# led_boost.net
KiCad netlist of a schematic drawn in Altium Designer
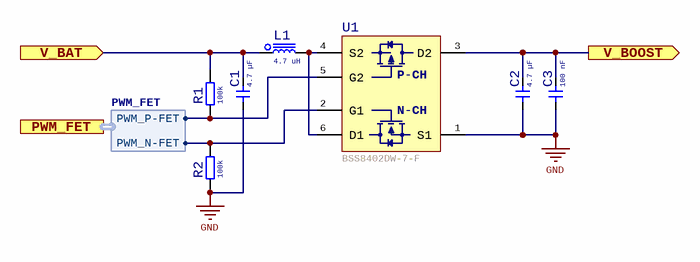
[diagram p0: led_boost.SchDoc]

(export (version "E")
  (design (tool "Eeschema 10.0.6"))
  (components
    (comp (ref "C1")
      (value "4.7 µF")
      (footprint "1608C")
      (description "SMD ceramic capacitor, X5R")
      (fields (field (name "MANUFACTURER") "Kemet") (field (name "VOLTAGE") "6,3"))
      (libsource (lib "Contronix") (part "CAP-NP"))
    )
    (comp (ref "C2")
      (value "4.7 µF")
      (footprint "1608C")
      (description "SMD ceramic capacitor, X5R")
      (fields (field (name "MANUFACTURER") "Kemet") (field (name "VOLTAGE") "6,3"))
      (libsource (lib "Contronix") (part "CAP-NP"))
    )
    (comp (ref "C3")
      (value "100 nF")
      (footprint "1005C")
      (description "SMD ceramic capacitor, X7R")
      (fields
        (field (name "MANUFACTURER") "Samsung Electro-Mechanics America, Inc.")
        (field (name "VOLTAGE") "6,3")
      )
      (libsource (lib "Contronix") (part "CAP-NP"))
    )
    (comp (ref "L1")
      (value "4.7 uH")
      (footprint "2012L")
      (description "Chip Inductor")
      (fields (field (name "MANUFACTURER") "Murata Electronics") (field (name "TOLERANCE") "30%"))
      (libsource (lib "Contronix") (part "INDUCTOR"))
    )
    (comp (ref "R1")
      (value "100k")
      (footprint "1005R")
      (description "SMD resistor")
      (fields (field (name "MANUFACTURER") "Yageo") (field (name "TOLERANCE") "1%"))
      (libsource (lib "Contronix") (part "RES"))
    )
    (comp (ref "R2")
      (value "100k")
      (footprint "1005R")
      (description "SMD resistor")
      (fields (field (name "MANUFACTURER") "Yageo") (field (name "TOLERANCE") "1%"))
      (libsource (lib "Contronix") (part "RES"))
    )
    (comp (ref "U1")
      (value "TRANS-FET-DUAL-N-P-6PIN")
      (footprint "TRANS-DUAL-SOT-363-6")
      (description "N and P-Channel MOSFET")
      (fields
        (field (name "MANUFACTURER") "Diodes Inc.")
        (field (name "VOLTAGE") "20")
        (field (name "MANUFACTURER P/N") "BSS8402DW-7-F")
      )
      (libsource (lib "Transistors") (part "TRANS-FET-DUAL-N-P-6PIN"))
    )
  )
  (nets
    (net (code "2") (name "/V_BAT") (class "Default")
      (node (ref "C1") (pin "2") (pinfunction "2_2") (pintype "passive"))
      (node (ref "L1") (pin "1") (pinfunction "1_1") (pintype "passive"))
      (node (ref "R1") (pin "2") (pinfunction "2_2") (pintype "passive"))
    )
    (net (code "3") (name "/V_BOOST") (class "Default")
      (node (ref "C2") (pin "2") (pinfunction "2_2") (pintype "passive"))
      (node (ref "C3") (pin "2") (pinfunction "2_2") (pintype "passive"))
      (node (ref "U1") (pin "3") (pinfunction "D2_3") (pintype "passive"))
    )
    (net (code "5") (name "GND") (class "Default")
      (node (ref "C1") (pin "1") (pinfunction "1_1") (pintype "passive"))
      (node (ref "C2") (pin "1") (pinfunction "1_1") (pintype "passive"))
      (node (ref "C3") (pin "1") (pinfunction "1_1") (pintype "passive"))
      (node (ref "R2") (pin "1") (pinfunction "1_1") (pintype "passive"))
      (node (ref "U1") (pin "1") (pinfunction "S1_1") (pintype "passive"))
    )
    (net (code "6") (name "Net-(U1-D1)") (class "Default")
      (node (ref "L1") (pin "2") (pinfunction "2_2") (pintype "passive"))
      (node (ref "U1") (pin "4") (pinfunction "S2_4") (pintype "passive"))
      (node (ref "U1") (pin "6") (pinfunction "D1_6") (pintype "passive"))
    )
    (net (code "7") (name "Net-(U1-G1)") (class "Default")
      (node (ref "R2") (pin "2") (pinfunction "2_2") (pintype "passive"))
      (node (ref "U1") (pin "2") (pinfunction "G1_2") (pintype "passive"))
    )
    (net (code "8") (name "Net-(U1-G2)") (class "Default")
      (node (ref "R1") (pin "1") (pinfunction "1_1") (pintype "passive"))
      (node (ref "U1") (pin "5") (pinfunction "G2_5") (pintype "passive"))
    )
  )
)
